# USB-PROG.net
KiCad netlist of a schematic drawn in Altium Designer
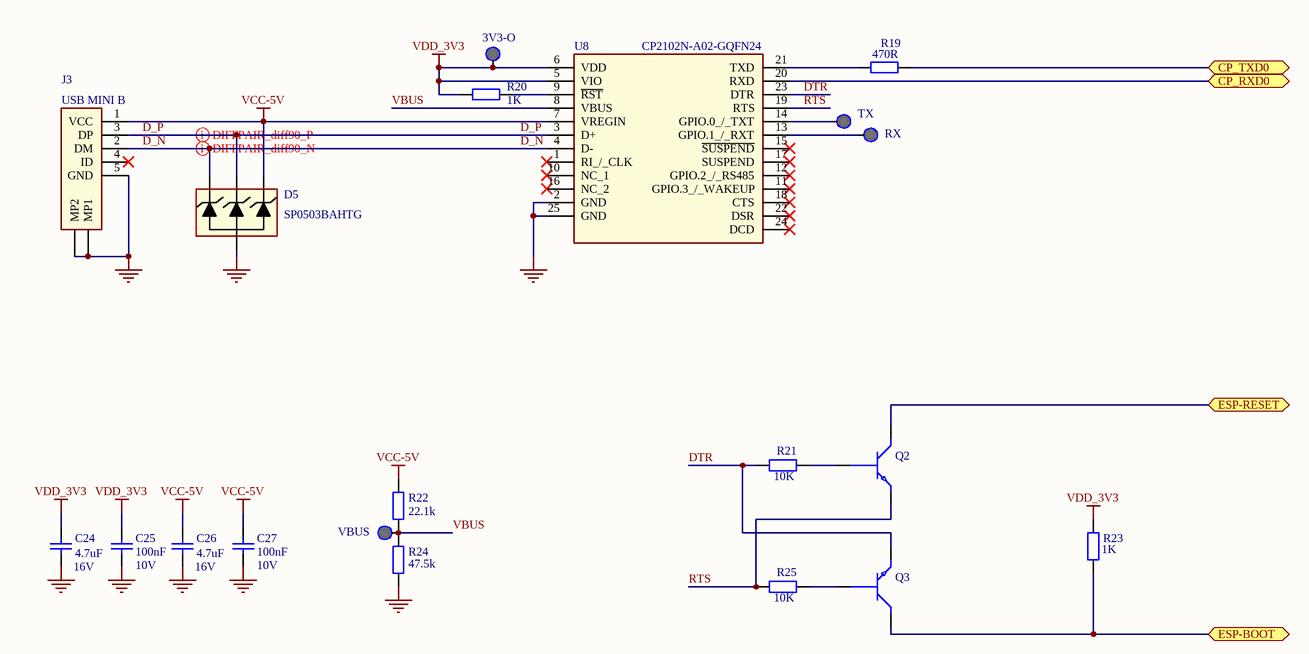
[diagram p0: USB-PROG.SchDoc]

(export (version "E")
  (design (tool "Eeschema 10.0.6"))
  (components
    (comp (ref "3V3-O")
      (value "Test Point")
      (footprint "TP")
      (fields (field (name "PART NUMBER") "MIS-000000003"))
      (libsource (lib "ESP32-Relay-Module") (part "TP"))
    )
    (comp (ref "C24")
      (value "Capacitor")
      (footprint "CAPC1608N")
      (fields
        (field (name "PART NUMBER") "CAP-000000047")
        (field (name "VALUE 1") "4.7uF")
        (field (name "VALUE 2") "16V")
      )
      (libsource (lib "ESP32-Relay-Module") (part "Capacitor"))
    )
    (comp (ref "C25")
      (value "Capacitor")
      (footprint "CAPC1608N")
      (fields
        (field (name "PART NUMBER") "CAP-000000005")
        (field (name "VALUE 1") "100nF")
        (field (name "VALUE 2") "10V")
      )
      (libsource (lib "ESP32-Relay-Module") (part "Capacitor"))
    )
    (comp (ref "C26")
      (value "Capacitor")
      (footprint "CAPC1608N")
      (fields
        (field (name "PART NUMBER") "CAP-000000047")
        (field (name "VALUE 1") "4.7uF")
        (field (name "VALUE 2") "16V")
      )
      (libsource (lib "ESP32-Relay-Module") (part "Capacitor"))
    )
    (comp (ref "C27")
      (value "Capacitor")
      (footprint "CAPC1608N")
      (fields
        (field (name "PART NUMBER") "CAP-000000005")
        (field (name "VALUE 1") "100nF")
        (field (name "VALUE 2") "10V")
      )
      (libsource (lib "ESP32-Relay-Module") (part "Capacitor"))
    )
    (comp (ref "D5")
      (value "SP0503BAHTG")
      (footprint "SOT192P237X122-4N")
      (fields (field (name "PART NUMBER") "TVS-000000002"))
      (libsource (lib "ESP32-Relay-Module") (part "SP0503BAHTG"))
    )
    (comp (ref "J3")
      (value "USB MINI B")
      (footprint "502237-0517")
      (fields (field (name "PART NUMBER") "CON-000000005"))
      (libsource (lib "ESP32-Relay-Module") (part "USB"))
    )
    (comp (ref "Q2")
      (value "MMSS8050-H-TP")
      (footprint "SOT95P245X112-3N")
      (fields (field (name "PART NUMBER") "TRP-000000003"))
      (libsource (lib "ESP32-Relay-Module") (part "NPN0"))
    )
    (comp (ref "Q3")
      (value "MMSS8050-H-TP")
      (footprint "SOT95P245X112-3N")
      (fields (field (name "PART NUMBER") "TRP-000000003"))
      (libsource (lib "ESP32-Relay-Module") (part "NPN0"))
    )
    (comp (ref "R19")
      (value "Resistor")
      (footprint "RESC1608N")
      (fields (field (name "PART NUMBER") "RES-000000016") (field (name "VALUE 1") "470R"))
      (libsource (lib "") (part "Resistor_1"))
    )
    (comp (ref "R20")
      (value "Resistor")
      (footprint "RESC1608N")
      (fields (field (name "PART NUMBER") "RES-000000006") (field (name "VALUE 1") "1K"))
      (libsource (lib "") (part "Resistor_1"))
    )
    (comp (ref "R21")
      (value "Resistor")
      (footprint "RESC1608N")
      (fields (field (name "PART NUMBER") "RES-000000001") (field (name "VALUE 1") "10K"))
      (libsource (lib "") (part "Resistor_1"))
    )
    (comp (ref "R22")
      (value "Resistor")
      (footprint "RESC1608N")
      (fields (field (name "PART NUMBER") "RES-000000017") (field (name "VALUE 1") "22.1k"))
      (libsource (lib "ESP32-Relay-Module") (part "Resistor"))
    )
    (comp (ref "R23")
      (value "Resistor")
      (footprint "RESC1608N")
      (fields (field (name "PART NUMBER") "RES-000000006") (field (name "VALUE 1") "1K"))
      (libsource (lib "ESP32-Relay-Module") (part "Resistor"))
    )
    (comp (ref "R24")
      (value "Resistor")
      (footprint "RESC1608N")
      (fields (field (name "PART NUMBER") "RES-000000018") (field (name "VALUE 1") "47.5k"))
      (libsource (lib "ESP32-Relay-Module") (part "Resistor"))
    )
    (comp (ref "R25")
      (value "Resistor")
      (footprint "RESC1608N")
      (fields (field (name "PART NUMBER") "RES-000000001") (field (name "VALUE 1") "10K"))
      (libsource (lib "") (part "Resistor_1"))
    )
    (comp (ref "RX")
      (value "Test Point")
      (footprint "TP")
      (fields (field (name "PART NUMBER") "MIS-000000003"))
      (libsource (lib "ESP32-Relay-Module") (part "TP"))
    )
    (comp (ref "TX")
      (value "Test Point")
      (footprint "TP")
      (fields (field (name "PART NUMBER") "MIS-000000003"))
      (libsource (lib "ESP32-Relay-Module") (part "TP"))
    )
    (comp (ref "U8")
      (value "CP2102N-A02-GQFN24")
      (footprint "QFN50P400X400X80-25N-D")
      (fields (field (name "PART NUMBER") "MIS-000000025"))
      (libsource (lib "ESP32-Relay-Module") (part "CP2102N-A02-GQFN24"))
    )
    (comp (ref "VBUS")
      (value "Test Point")
      (footprint "TP")
      (fields (field (name "PART NUMBER") "MIS-000000003"))
      (libsource (lib "ESP32-Relay-Module") (part "TP"))
    )
  )
  (nets
    (net (code "1") (name "/CP_RXD0") (class "Default")
      (node (ref "U8") (pin "20") (pinfunction "RXD_20") (pintype "passive"))
    )
    (net (code "2") (name "/CP_TXD0") (class "Default")
      (node (ref "R19") (pin "2") (pinfunction "2_2") (pintype "passive"))
    )
    (net (code "3") (name "/DTR") (class "Default")
      (node (ref "Q3") (pin "2") (pinfunction "E_2") (pintype "passive"))
      (node (ref "R21") (pin "1") (pinfunction "1_1") (pintype "passive"))
      (node (ref "U8") (pin "23") (pinfunction "DTR_23") (pintype "passive"))
    )
    (net (code "4") (name "/D_N") (class "Default")
      (node (ref "D5") (pin "2") (pinfunction "2_2") (pintype "passive"))
      (node (ref "J3") (pin "2") (pinfunction "DM_2") (pintype "passive"))
      (node (ref "U8") (pin "4") (pinfunction "D-_4") (pintype "passive"))
    )
    (net (code "5") (name "/D_P") (class "Default")
      (node (ref "D5") (pin "3") (pinfunction "3_3") (pintype "passive"))
      (node (ref "J3") (pin "3") (pinfunction "DP_3") (pintype "passive"))
      (node (ref "U8") (pin "3") (pinfunction "D+_3") (pintype "passive"))
    )
    (net (code "6") (name "/ESP-BOOT") (class "Default")
      (node (ref "Q3") (pin "3") (pinfunction "C_3") (pintype "passive"))
      (node (ref "R23") (pin "1") (pinfunction "1_1") (pintype "passive"))
    )
    (net (code "7") (name "/ESP-RESET") (class "Default")
      (node (ref "Q2") (pin "3") (pinfunction "C_3") (pintype "passive"))
    )
    (net (code "8") (name "/RTS") (class "Default")
      (node (ref "Q2") (pin "2") (pinfunction "E_2") (pintype "passive"))
      (node (ref "R25") (pin "1") (pinfunction "1_1") (pintype "passive"))
      (node (ref "U8") (pin "19") (pinfunction "RTS_19") (pintype "passive"))
    )
    (net (code "9") (name "/VBUS") (class "Default")
      (node (ref "R22") (pin "1") (pinfunction "1_1") (pintype "passive"))
      (node (ref "R24") (pin "2") (pinfunction "2_2") (pintype "passive"))
      (node (ref "U8") (pin "8") (pinfunction "VBUS_8") (pintype "passive"))
      (node (ref "VBUS") (pin "1") (pinfunction "1_1") (pintype "passive"))
    )
    (net (code "10") (name "GND") (class "Default")
      (node (ref "C24") (pin "1") (pinfunction "1_1") (pintype "passive"))
      (node (ref "C25") (pin "1") (pinfunction "1_1") (pintype "passive"))
      (node (ref "C26") (pin "1") (pinfunction "1_1") (pintype "passive"))
      (node (ref "C27") (pin "1") (pinfunction "1_1") (pintype "passive"))
      (node (ref "D5") (pin "1") (pinfunction "1_1") (pintype "passive"))
      (node (ref "J3") (pin "5") (pinfunction "GND_5") (pintype "passive"))
      (node (ref "J3") (pin "MP1") (pinfunction "MP1_MP1") (pintype "passive"))
      (node (ref "J3") (pin "MP2") (pinfunction "MP2_MP2") (pintype "passive"))
      (node (ref "R24") (pin "1") (pinfunction "1_1") (pintype "passive"))
      (node (ref "U8") (pin "2") (pinfunction "GND_2") (pintype "passive"))
      (node (ref "U8") (pin "25") (pinfunction "GND_25") (pintype "passive"))
    )
    (net (code "11") (name "Net-(Q2-B)") (class "Default")
      (node (ref "Q2") (pin "1") (pinfunction "B_1") (pintype "passive"))
      (node (ref "R21") (pin "2") (pinfunction "2_2") (pintype "passive"))
    )
    (net (code "12") (name "Net-(Q3-B)") (class "Default")
      (node (ref "Q3") (pin "1") (pinfunction "B_1") (pintype "passive"))
      (node (ref "R25") (pin "2") (pinfunction "2_2") (pintype "passive"))
    )
    (net (code "13") (name "Net-(U8-GPIO.0_{slash}_TXT)") (class "Default")
      (node (ref "TX") (pin "1") (pinfunction "1_1") (pintype "passive"))
      (node (ref "U8") (pin "14") (pinfunction "GPIO.0_/_TXT_14") (pintype "passive"))
    )
    (net (code "14") (name "Net-(U8-GPIO.1_{slash}_RXT)") (class "Default")
      (node (ref "RX") (pin "1") (pinfunction "1_1") (pintype "passive"))
      (node (ref "U8") (pin "13") (pinfunction "GPIO.1_/_RXT_13") (pintype "passive"))
    )
    (net (code "15") (name "Net-(U8-TXD)") (class "Default")
      (node (ref "R19") (pin "1") (pinfunction "1_1") (pintype "passive"))
      (node (ref "U8") (pin "21") (pinfunction "TXD_21") (pintype "passive"))
    )
    (net (code "16") (name "Net-(U8-~{RST})") (class "Default")
      (node (ref "R20") (pin "2") (pinfunction "2_2") (pintype "passive"))
      (node (ref "U8") (pin "9") (pinfunction "~{RST}_9") (pintype "passive"))
    )
    (net (code "17") (name "VCC-5V") (class "Default")
      (node (ref "C26") (pin "2") (pinfunction "2_2") (pintype "passive"))
      (node (ref "C27") (pin "2") (pinfunction "2_2") (pintype "passive"))
      (node (ref "D5") (pin "4") (pinfunction "4_4") (pintype "passive"))
      (node (ref "J3") (pin "1") (pinfunction "VCC_1") (pintype "passive"))
      (node (ref "R22") (pin "2") (pinfunction "2_2") (pintype "passive"))
      (node (ref "U8") (pin "7") (pinfunction "VREGIN_7") (pintype "passive"))
    )
    (net (code "18") (name "VDD_3V3") (class "Default")
      (node (ref "3V3-O") (pin "1") (pinfunction "1_1") (pintype "passive"))
      (node (ref "C24") (pin "2") (pinfunction "2_2") (pintype "passive"))
      (node (ref "C25") (pin "2") (pinfunction "2_2") (pintype "passive"))
      (node (ref "R20") (pin "1") (pinfunction "1_1") (pintype "passive"))
      (node (ref "R23") (pin "2") (pinfunction "2_2") (pintype "passive"))
      (node (ref "U8") (pin "5") (pinfunction "VIO_5") (pintype "passive"))
      (node (ref "U8") (pin "6") (pinfunction "VDD_6") (pintype "passive"))
    )
    (net (code "19") (name "unconnected-(J3-ID-Pad4)") (class "Default")
      (node (ref "J3") (pin "4") (pinfunction "ID_4") (pintype "passive+no_connect"))
    )
    (net (code "20") (name "unconnected-(U8-CTS-Pad18)") (class "Default")
      (node (ref "U8") (pin "18") (pinfunction "CTS_18") (pintype "passive+no_connect"))
    )
    (net (code "21") (name "unconnected-(U8-DCD-Pad24)") (class "Default")
      (node (ref "U8") (pin "24") (pinfunction "DCD_24") (pintype "passive+no_connect"))
    )
    (net (code "22") (name "unconnected-(U8-DSR-Pad22)") (class "Default")
      (node (ref "U8") (pin "22") (pinfunction "DSR_22") (pintype "passive+no_connect"))
    )
    (net (code "23") (name "unconnected-(U8-GPIO.2_{slash}_RS485-Pad12)") (class "Default")
      (node (ref "U8") (pin "12") (pinfunction "GPIO.2_/_RS485_12") (pintype "passive+no_connect"))
    )
    (net (code "24") (name "unconnected-(U8-GPIO.3_{slash}_WAKEUP-Pad11)") (class "Default")
      (node (ref "U8") (pin "11") (pinfunction "GPIO.3_/_WAKEUP_11") (pintype "passive+no_connect"))
    )
    (net (code "25") (name "unconnected-(U8-NC_1-Pad10)") (class "Default")
      (node (ref "U8") (pin "10") (pinfunction "NC_1_10") (pintype "passive+no_connect"))
    )
    (net (code "26") (name "unconnected-(U8-NC_2-Pad16)") (class "Default")
      (node (ref "U8") (pin "16") (pinfunction "NC_2_16") (pintype "passive+no_connect"))
    )
    (net (code "27") (name "unconnected-(U8-RI_{slash}_CLK-Pad1)") (class "Default")
      (node (ref "U8") (pin "1") (pinfunction "RI_/_CLK_1") (pintype "passive+no_connect"))
    )
    (net (code "28") (name "unconnected-(U8-SUSPEND-Pad17)") (class "Default")
      (node (ref "U8") (pin "17") (pinfunction "SUSPEND_17") (pintype "passive+no_connect"))
    )
    (net (code "29") (name "unconnected-(U8-~{SUSPEND}-Pad15)") (class "Default")
      (node (ref "U8") (pin "15") (pinfunction "~{SUSPEND}_15") (pintype "passive+no_connect"))
    )
  )
)
